# RTC_unit.net
KiCad netlist of a schematic drawn in Altium Designer
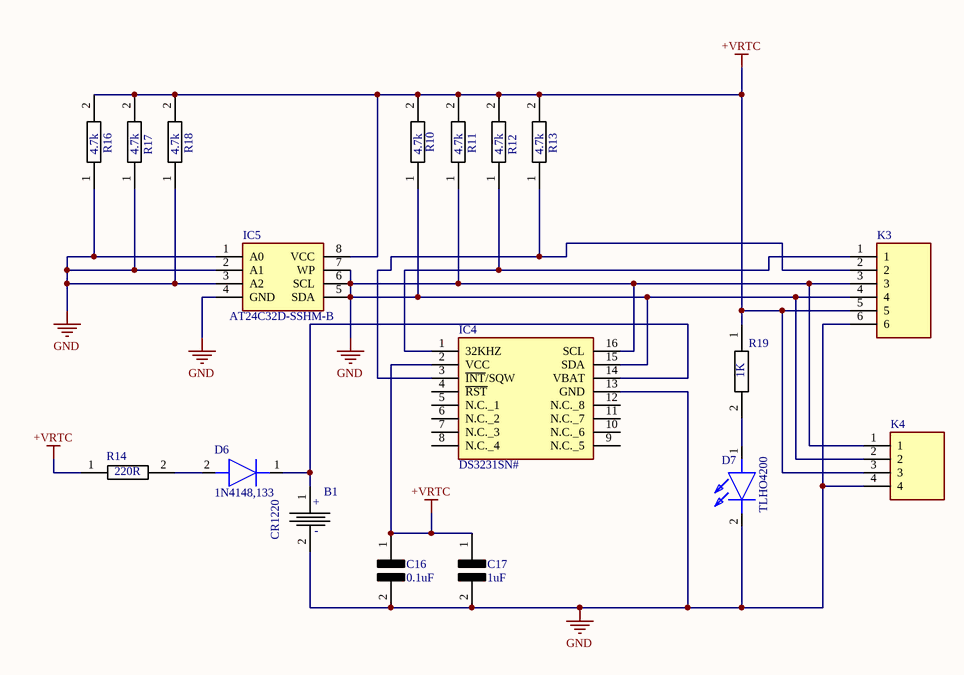
[diagram p0: RTC_unit.SchDoc]

(export (version "E")
  (design (tool "Eeschema 10.0.6"))
  (components
    (comp (ref "B1")
      (value "CR1220")
      (footprint "SamacSys:CR1220HSMD")
      (description "Integrated Circuit")
      (fields (field (name "MANUFACTURER_PART_NUMBER") "CR1220-H-SMD"))
      (libsource (lib "Schlib1") (part "CR1220-H-SMD"))
    )
    (comp (ref "C16")
      (value "0.1uF")
      (footprint "C0805")
      (description "0805 ceramic capacitor")
      (fields
        (field (name "MANUFACTURER_PART_NUMBER") "GRM188R71H103KA01D")
        (field (name "MOUSER PART NUMBER") "81-GRM39X103K50D")
      )
      (libsource (lib "Schlib1") (part "KeramischeC0805_1"))
    )
    (comp (ref "C17")
      (value "1uF")
      (footprint "C0805")
      (description "0805 ceramic capacitor")
      (fields
        (field (name "MANUFACTURER_PART_NUMBER") "GRM188R71H103KA01D")
        (field (name "MOUSER PART NUMBER") "81-GRM39X103K50D")
      )
      (libsource (lib "Schlib1") (part "KeramischeC0805_1"))
    )
    (comp (ref "D6")
      (value "1N4148,133")
      (footprint "SamacSys:DIOAD1165W56L425D185")
      (description "Diode")
      (fields (field (name "MOUSER PART NUMBER") "771-1N4148,133"))
      (libsource (lib "Schlib1") (part "1N4148,133"))
    )
    (comp (ref "D7")
      (value "TLHO4200")
      (footprint "SamacSys:TLHO4200")
      (description "LED")
      (libsource (lib "Schlib1") (part "TLHO4200"))
    )
    (comp (ref "IC4")
      (value "DS3231SN#")
      (footprint "SamacSys:SOIC127P1032X265-16N")
      (description "Integrated Circuit")
      (fields (field (name "MOUSER PART NUMBER") "700-DS3231SN#"))
      (libsource (lib "Schlib1") (part "DS3231SN#"))
    )
    (comp (ref "IC5")
      (value "AT24C32D-SSHM-B")
      (footprint "SamacSys:SOIC127P600X175-8N")
      (description "Integrated Circuit")
      (fields (field (name "MOUSER PART NUMBER") "556-AT24C32D-SSHM-B"))
      (libsource (lib "Schlib1") (part "AT24C32D-SSHM-B"))
    )
    (comp (ref "K3")
      (value "2212S-06SG-85")
      (footprint "SamacSys:RHDR6W74P0X254_1X6_1574X250X850P")
      (description "Connector")
      (libsource (lib "Schlib1") (part "2212S-06SG-85"))
    )
    (comp (ref "K4")
      (value "2212S-04SG-85")
      (footprint "SamacSys:2212S04SG85")
      (description "Connector")
      (libsource (lib "Schlib1") (part "2212S-04SG-85"))
    )
    (comp (ref "R10")
      (value "4.7k")
      (footprint "C0805")
      (description "Resistor0805")
      (fields
        (field (name "MANUFACTURER_PART_NUMBER") "CRCW08050000Z0EAHP")
        (field (name "MOUSER PART NUMBER") "71-CRCW08050000Z0EAH")
      )
      (libsource (lib "Schlib1") (part "Resistor0805"))
    )
    (comp (ref "R11")
      (value "4.7k")
      (footprint "C0805")
      (description "Resistor0805")
      (fields
        (field (name "MANUFACTURER_PART_NUMBER") "CRCW08050000Z0EAHP")
        (field (name "MOUSER PART NUMBER") "71-CRCW08050000Z0EAH")
      )
      (libsource (lib "Schlib1") (part "Resistor0805"))
    )
    (comp (ref "R12")
      (value "4.7k")
      (footprint "C0805")
      (description "Resistor0805")
      (fields
        (field (name "MANUFACTURER_PART_NUMBER") "CRCW08050000Z0EAHP")
        (field (name "MOUSER PART NUMBER") "71-CRCW08050000Z0EAH")
      )
      (libsource (lib "Schlib1") (part "Resistor0805"))
    )
    (comp (ref "R13")
      (value "4.7k")
      (footprint "C0805")
      (description "Resistor0805")
      (fields
        (field (name "MANUFACTURER_PART_NUMBER") "CRCW08050000Z0EAHP")
        (field (name "MOUSER PART NUMBER") "71-CRCW08050000Z0EAH")
      )
      (libsource (lib "Schlib1") (part "Resistor0805"))
    )
    (comp (ref "R14")
      (value "220R")
      (footprint "C0805")
      (description "Resistor0805")
      (fields
        (field (name "MANUFACTURER_PART_NUMBER") "CRCW08050000Z0EAHP")
        (field (name "MOUSER PART NUMBER") "71-CRCW08050000Z0EAH")
      )
      (libsource (lib "Schlib1") (part "Resistor0805"))
    )
    (comp (ref "R16")
      (value "4.7k")
      (footprint "C0805")
      (description "Resistor0805")
      (fields
        (field (name "MANUFACTURER_PART_NUMBER") "CRCW08050000Z0EAHP")
        (field (name "MOUSER PART NUMBER") "71-CRCW08050000Z0EAH")
      )
      (libsource (lib "Schlib1") (part "Resistor0805"))
    )
    (comp (ref "R17")
      (value "4.7k")
      (footprint "C0805")
      (description "Resistor0805")
      (fields
        (field (name "MANUFACTURER_PART_NUMBER") "CRCW08050000Z0EAHP")
        (field (name "MOUSER PART NUMBER") "71-CRCW08050000Z0EAH")
      )
      (libsource (lib "Schlib1") (part "Resistor0805"))
    )
    (comp (ref "R18")
      (value "4.7k")
      (footprint "C0805")
      (description "Resistor0805")
      (fields
        (field (name "MANUFACTURER_PART_NUMBER") "CRCW08050000Z0EAHP")
        (field (name "MOUSER PART NUMBER") "71-CRCW08050000Z0EAH")
      )
      (libsource (lib "Schlib1") (part "Resistor0805"))
    )
    (comp (ref "R19")
      (value "1K")
      (footprint "C0805")
      (description "Resistor0805")
      (fields
        (field (name "MANUFACTURER_PART_NUMBER") "CRCW08050000Z0EAHP")
        (field (name "MOUSER PART NUMBER") "71-CRCW08050000Z0EAH")
      )
      (libsource (lib "Schlib1") (part "Resistor0805"))
    )
  )
  (nets
    (net (code "1") (name "+VRTC") (class "Default")
      (node (ref "C16") (pin "1") (pinfunction "1_1") (pintype "passive"))
      (node (ref "C17") (pin "1") (pinfunction "1_1") (pintype "passive"))
      (node (ref "IC4") (pin "2") (pinfunction "VCC_2") (pintype "passive"))
      (node (ref "IC5") (pin "8") (pinfunction "VCC_8") (pintype "passive"))
      (node (ref "K3") (pin "5") (pinfunction "5_5") (pintype "passive"))
      (node (ref "K4") (pin "3") (pinfunction "3_3") (pintype "passive"))
      (node (ref "R10") (pin "2") (pinfunction "2_2") (pintype "passive"))
      (node (ref "R11") (pin "2") (pinfunction "2_2") (pintype "passive"))
      (node (ref "R12") (pin "2") (pinfunction "2_2") (pintype "passive"))
      (node (ref "R13") (pin "2") (pinfunction "2_2") (pintype "passive"))
      (node (ref "R14") (pin "1") (pinfunction "1_1") (pintype "passive"))
      (node (ref "R16") (pin "2") (pinfunction "2_2") (pintype "passive"))
      (node (ref "R17") (pin "2") (pinfunction "2_2") (pintype "passive"))
      (node (ref "R18") (pin "2") (pinfunction "2_2") (pintype "passive"))
      (node (ref "R19") (pin "1") (pinfunction "1_1") (pintype "passive"))
    )
    (net (code "2") (name "GND") (class "Default")
      (node (ref "B1") (pin "2") (pinfunction "2_2") (pintype "passive"))
      (node (ref "C16") (pin "2") (pinfunction "2_2") (pintype "passive"))
      (node (ref "C17") (pin "2") (pinfunction "2_2") (pintype "passive"))
      (node (ref "D7") (pin "2") (pinfunction "K_2") (pintype "passive"))
      (node (ref "IC4") (pin "13") (pinfunction "GND_13") (pintype "passive"))
      (node (ref "IC4") (pin "15") (pinfunction "SDA_15") (pintype "passive"))
      (node (ref "IC4") (pin "16") (pinfunction "SCL_16") (pintype "passive"))
      (node (ref "IC5") (pin "1") (pinfunction "A0_1") (pintype "passive"))
      (node (ref "IC5") (pin "2") (pinfunction "A1_2") (pintype "passive"))
      (node (ref "IC5") (pin "3") (pinfunction "A2_3") (pintype "passive"))
      (node (ref "IC5") (pin "4") (pinfunction "GND_4") (pintype "passive"))
      (node (ref "IC5") (pin "5") (pinfunction "SDA_5") (pintype "passive"))
      (node (ref "IC5") (pin "6") (pinfunction "SCL_6") (pintype "passive"))
      (node (ref "IC5") (pin "7") (pinfunction "WP_7") (pintype "passive"))
      (node (ref "K3") (pin "3") (pinfunction "3_3") (pintype "passive"))
      (node (ref "K3") (pin "4") (pinfunction "4_4") (pintype "passive"))
      (node (ref "K3") (pin "6") (pinfunction "6_6") (pintype "passive"))
      (node (ref "K4") (pin "1") (pinfunction "1_1") (pintype "passive"))
      (node (ref "K4") (pin "2") (pinfunction "2_2") (pintype "passive"))
      (node (ref "K4") (pin "4") (pinfunction "4_4") (pintype "passive"))
      (node (ref "R10") (pin "1") (pinfunction "1_1") (pintype "passive"))
      (node (ref "R11") (pin "1") (pinfunction "1_1") (pintype "passive"))
      (node (ref "R16") (pin "1") (pinfunction "1_1") (pintype "passive"))
      (node (ref "R17") (pin "1") (pinfunction "1_1") (pintype "passive"))
      (node (ref "R18") (pin "1") (pinfunction "1_1") (pintype "passive"))
    )
    (net (code "3") (name "Net-(D6-A)") (class "Default")
      (node (ref "D6") (pin "2") (pinfunction "A_2") (pintype "passive"))
      (node (ref "R14") (pin "2") (pinfunction "2_2") (pintype "passive"))
    )
    (net (code "4") (name "Net-(D6-K)") (class "Default")
      (node (ref "B1") (pin "1") (pinfunction "1_1") (pintype "passive"))
      (node (ref "D6") (pin "1") (pinfunction "K_1") (pintype "passive"))
      (node (ref "IC4") (pin "14") (pinfunction "VBAT_14") (pintype "passive"))
    )
    (net (code "5") (name "Net-(D7-A)") (class "Default")
      (node (ref "D7") (pin "1") (pinfunction "A_1") (pintype "passive"))
      (node (ref "R19") (pin "2") (pinfunction "2_2") (pintype "passive"))
    )
    (net (code "6") (name "Net-(IC4-32KHZ)") (class "Default")
      (node (ref "IC4") (pin "1") (pinfunction "32KHZ_1") (pintype "passive"))
      (node (ref "K3") (pin "1") (pinfunction "1_1") (pintype "passive"))
      (node (ref "R12") (pin "1") (pinfunction "1_1") (pintype "passive"))
    )
    (net (code "7") (name "Net-(IC4-~{INT}{slash}SQW)") (class "Default")
      (node (ref "IC4") (pin "3") (pinfunction "~{INT}/SQW_3") (pintype "passive"))
      (node (ref "K3") (pin "2") (pinfunction "2_2") (pintype "passive"))
      (node (ref "R13") (pin "1") (pinfunction "1_1") (pintype "passive"))
    )
    (net (code "8") (name "unconnected-(IC4-N.C._1-Pad5)") (class "Default")
      (node (ref "IC4") (pin "5") (pinfunction "N.C._1_5") (pintype "passive"))
    )
    (net (code "9") (name "unconnected-(IC4-N.C._2-Pad6)") (class "Default")
      (node (ref "IC4") (pin "6") (pinfunction "N.C._2_6") (pintype "passive"))
    )
    (net (code "10") (name "unconnected-(IC4-N.C._3-Pad7)") (class "Default")
      (node (ref "IC4") (pin "7") (pinfunction "N.C._3_7") (pintype "passive"))
    )
    (net (code "11") (name "unconnected-(IC4-N.C._4-Pad8)") (class "Default")
      (node (ref "IC4") (pin "8") (pinfunction "N.C._4_8") (pintype "passive"))
    )
    (net (code "12") (name "unconnected-(IC4-N.C._5-Pad9)") (class "Default")
      (node (ref "IC4") (pin "9") (pinfunction "N.C._5_9") (pintype "passive"))
    )
    (net (code "13") (name "unconnected-(IC4-N.C._6-Pad10)") (class "Default")
      (node (ref "IC4") (pin "10") (pinfunction "N.C._6_10") (pintype "passive"))
    )
    (net (code "14") (name "unconnected-(IC4-N.C._7-Pad11)") (class "Default")
      (node (ref "IC4") (pin "11") (pinfunction "N.C._7_11") (pintype "passive"))
    )
    (net (code "15") (name "unconnected-(IC4-N.C._8-Pad12)") (class "Default")
      (node (ref "IC4") (pin "12") (pinfunction "N.C._8_12") (pintype "passive"))
    )
    (net (code "16") (name "unconnected-(IC4-~{RST}-Pad4)") (class "Default")
      (node (ref "IC4") (pin "4") (pinfunction "~{RST}_4") (pintype "passive"))
    )
  )
)
